# Battery_Protection.net
KiCad netlist of a schematic drawn in Altium Designer
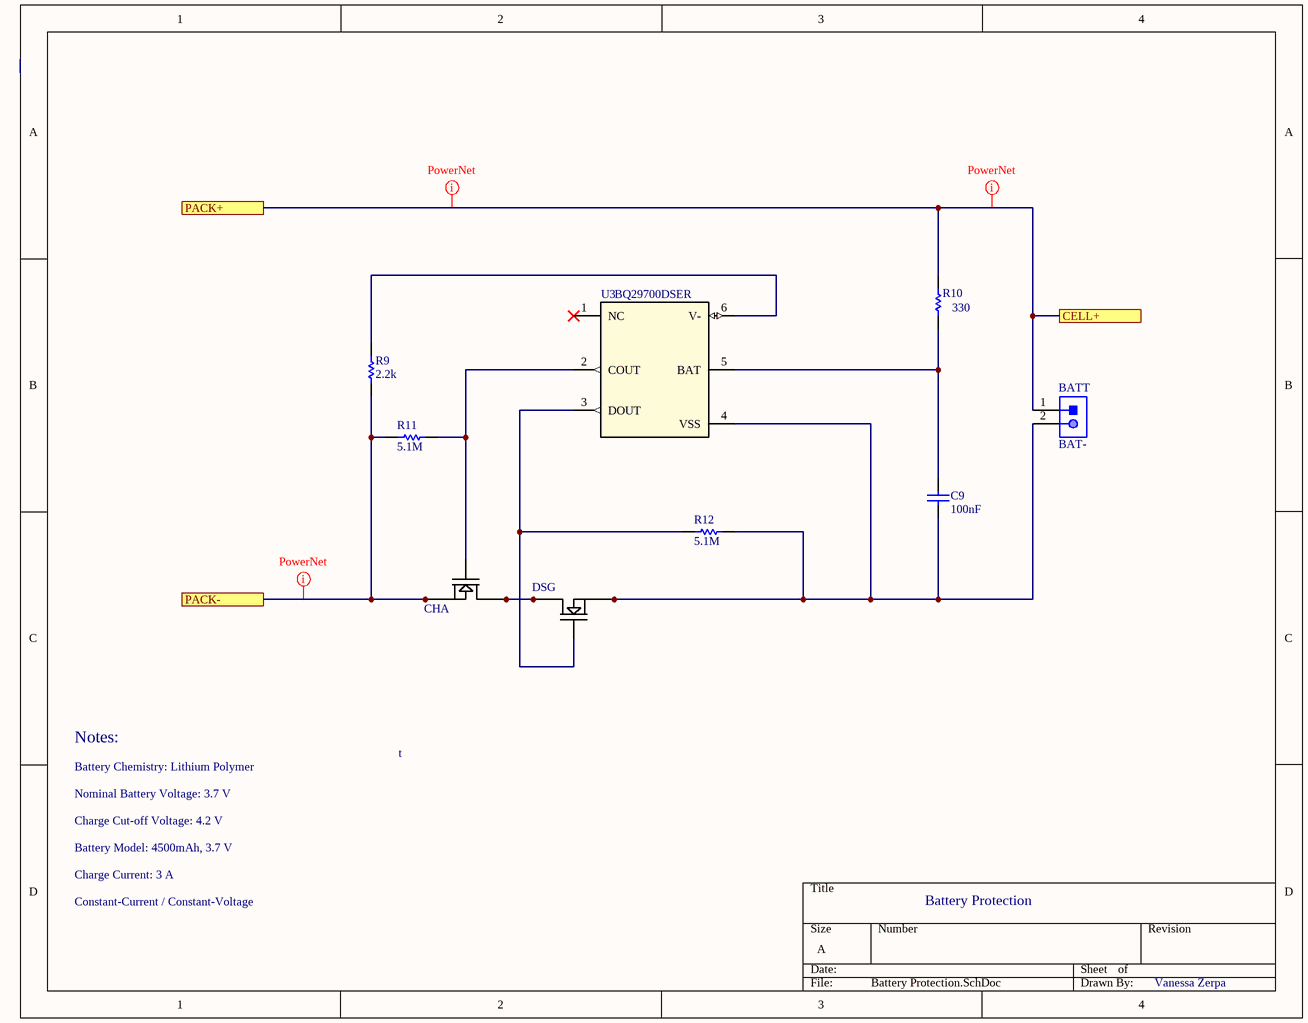
[diagram p0: Battery Protection.SchDoc]

(export (version "E")
  (design (tool "Eeschema 10.0.6"))
  (components
    (comp (ref "BATT")
      (value "BAT-")
      (footprint "JST-S2B-PH-K-S_V")
      (fields (field (name "TOLERANCE") "20%"))
      (libsource (lib "Altium Content Vault") (part "CN-1P-M-R2"))
    )
    (comp (ref "C9")
      (value "100nF")
      (footprint "CAPC2013X94X50NL20T25")
      (fields
        (field (name "MANUFACTURER") "AVX Interconnect / Elco")
        (field (name "PART NUMBER") "08055C104KAT4A")
      )
      (libsource (lib "Altium Content Vault") (part "CAP"))
    )
    (comp (ref "CHA")
      (value "CSD16406Q3")
      (footprint "DQG0008A")
      (description "No Description Available")
      (fields (field (name "COPYRIGHT") "Copyright (C) 2021 Ultra Librarian. All rights reserved."))
      (libsource (lib "MOSFET") (part "CSD16406Q3"))
    )
    (comp (ref "DSG")
      (value "CSD16406Q3")
      (footprint "DQG0008A")
      (description "No Description Available")
      (fields (field (name "COPYRIGHT") "Copyright (C) 2021 Ultra Librarian. All rights reserved."))
      (libsource (lib "MOSFET") (part "CSD16406Q3"))
    )
    (comp (ref "R9")
      (value "2.2k")
      (footprint "RESC2013X60X40LL20T25")
      (fields (field (name "MANUFACTURER") "Panasonic") (field (name "PART NUMBER") "ERA6AEB222V"))
      (libsource (lib "Altium Content Vault") (part "RES"))
    )
    (comp (ref "R10")
      (value "330")
      (footprint "RESC2013X70X40ML20T20")
      (fields (field (name "MANUFACTURER") "Panasonic") (field (name "PART NUMBER") "ERJ-6GEYJ331V"))
      (libsource (lib "Altium Content Vault") (part "RES"))
    )
    (comp (ref "R11")
      (value "5.1M")
      (footprint "RESC2013X70X40ML20T20")
      (fields (field (name "PART NUMBER") "ERJ-6GEYJ515V") (field (name "MANUFACTURER") "Panasonic"))
      (libsource (lib "Altium Content Vault") (part "RES"))
    )
    (comp (ref "R12")
      (value "5.1M")
      (footprint "RESC2013X70X40ML20T20")
      (fields (field (name "PART NUMBER") "ERJ-6GEYJ515V") (field (name "MANUFACTURER") "Panasonic"))
      (libsource (lib "Altium Content Vault") (part "RES"))
    )
    (comp (ref "U3")
      (value "BQ29700DSER")
      (footprint "DSE0006A")
      (description "No Description Available")
      (fields (field (name "COPYRIGHT") "Copyright (C) 2021 Ultra Librarian. All rights reserved."))
      (libsource (lib "BatteryProtection") (part "BQ29700DSER"))
    )
  )
  (nets
    (net (code "1") (name "/CELL+") (class "Default")
      (node (ref "BATT") (pin "1") (pinfunction "1_1") (pintype "passive"))
      (node (ref "R10") (pin "2") (pinfunction "2_2") (pintype "passive"))
    )
    (net (code "2") (name "/PACK-") (class "Default")
      (node (ref "CHA") (pin "1") (pinfunction "Source_1") (pintype "passive"))
      (node (ref "CHA") (pin "2") (pinfunction "Source_2") (pintype "passive"))
      (node (ref "CHA") (pin "3") (pinfunction "Source_3") (pintype "passive"))
      (node (ref "R11") (pin "1") (pinfunction "1_1") (pintype "passive"))
      (node (ref "R9") (pin "1") (pinfunction "1_1") (pintype "passive"))
    )
    (net (code "3") (name "Net-(CHA-Drain-Pad5)") (class "Default")
      (node (ref "CHA") (pin "5") (pinfunction "Drain_5") (pintype "passive"))
      (node (ref "CHA") (pin "6") (pinfunction "Drain_6") (pintype "passive"))
      (node (ref "CHA") (pin "7") (pinfunction "Drain_7") (pintype "passive"))
      (node (ref "CHA") (pin "8") (pinfunction "Drain_8") (pintype "passive"))
      (node (ref "CHA") (pin "9") (pinfunction "Drain_9") (pintype "passive"))
      (node (ref "DSG") (pin "5") (pinfunction "Drain_5") (pintype "passive"))
      (node (ref "DSG") (pin "6") (pinfunction "Drain_6") (pintype "passive"))
      (node (ref "DSG") (pin "7") (pinfunction "Drain_7") (pintype "passive"))
      (node (ref "DSG") (pin "8") (pinfunction "Drain_8") (pintype "passive"))
      (node (ref "DSG") (pin "9") (pinfunction "Drain_9") (pintype "passive"))
    )
    (net (code "4") (name "Net-(CHA-Gate)") (class "Default")
      (node (ref "CHA") (pin "4") (pinfunction "Gate_4") (pintype "passive"))
      (node (ref "R11") (pin "2") (pinfunction "2_2") (pintype "passive"))
      (node (ref "U3") (pin "2") (pinfunction "COUT_2") (pintype "output"))
    )
    (net (code "5") (name "Net-(DSG-Gate)") (class "Default")
      (node (ref "DSG") (pin "4") (pinfunction "Gate_4") (pintype "passive"))
      (node (ref "R12") (pin "1") (pinfunction "1_1") (pintype "passive"))
      (node (ref "U3") (pin "3") (pinfunction "DOUT_3") (pintype "output"))
    )
    (net (code "6") (name "Net-(U3-BAT)") (class "Default")
      (node (ref "C9") (pin "2") (pinfunction "2_2") (pintype "passive"))
      (node (ref "R10") (pin "1") (pinfunction "1_1") (pintype "passive"))
      (node (ref "U3") (pin "5") (pinfunction "BAT_5") (pintype "power_in"))
    )
    (net (code "7") (name "Net-(U3-V-)") (class "Default")
      (node (ref "R9") (pin "2") (pinfunction "2_2") (pintype "passive"))
      (node (ref "U3") (pin "6") (pinfunction "V-_6") (pintype "bidirectional"))
    )
    (net (code "8") (name "Net-(U3-VSS)") (class "Default")
      (node (ref "BATT") (pin "2") (pinfunction "2_2") (pintype "passive"))
      (node (ref "C9") (pin "1") (pinfunction "1_1") (pintype "passive"))
      (node (ref "DSG") (pin "1") (pinfunction "Source_1") (pintype "passive"))
      (node (ref "DSG") (pin "2") (pinfunction "Source_2") (pintype "passive"))
      (node (ref "DSG") (pin "3") (pinfunction "Source_3") (pintype "passive"))
      (node (ref "R12") (pin "2") (pinfunction "2_2") (pintype "passive"))
      (node (ref "U3") (pin "4") (pinfunction "VSS_4") (pintype "power_in"))
    )
    (net (code "9") (name "unconnected-(U3-NC-Pad1)") (class "Default")
      (node (ref "U3") (pin "1") (pinfunction "NC_1") (pintype "passive+no_connect"))
    )
  )
)
